# LB_BIT_iX_1IN_1OUT-SMALL-v03_1_1x.net
KiCad netlist of a schematic drawn in EAGLE
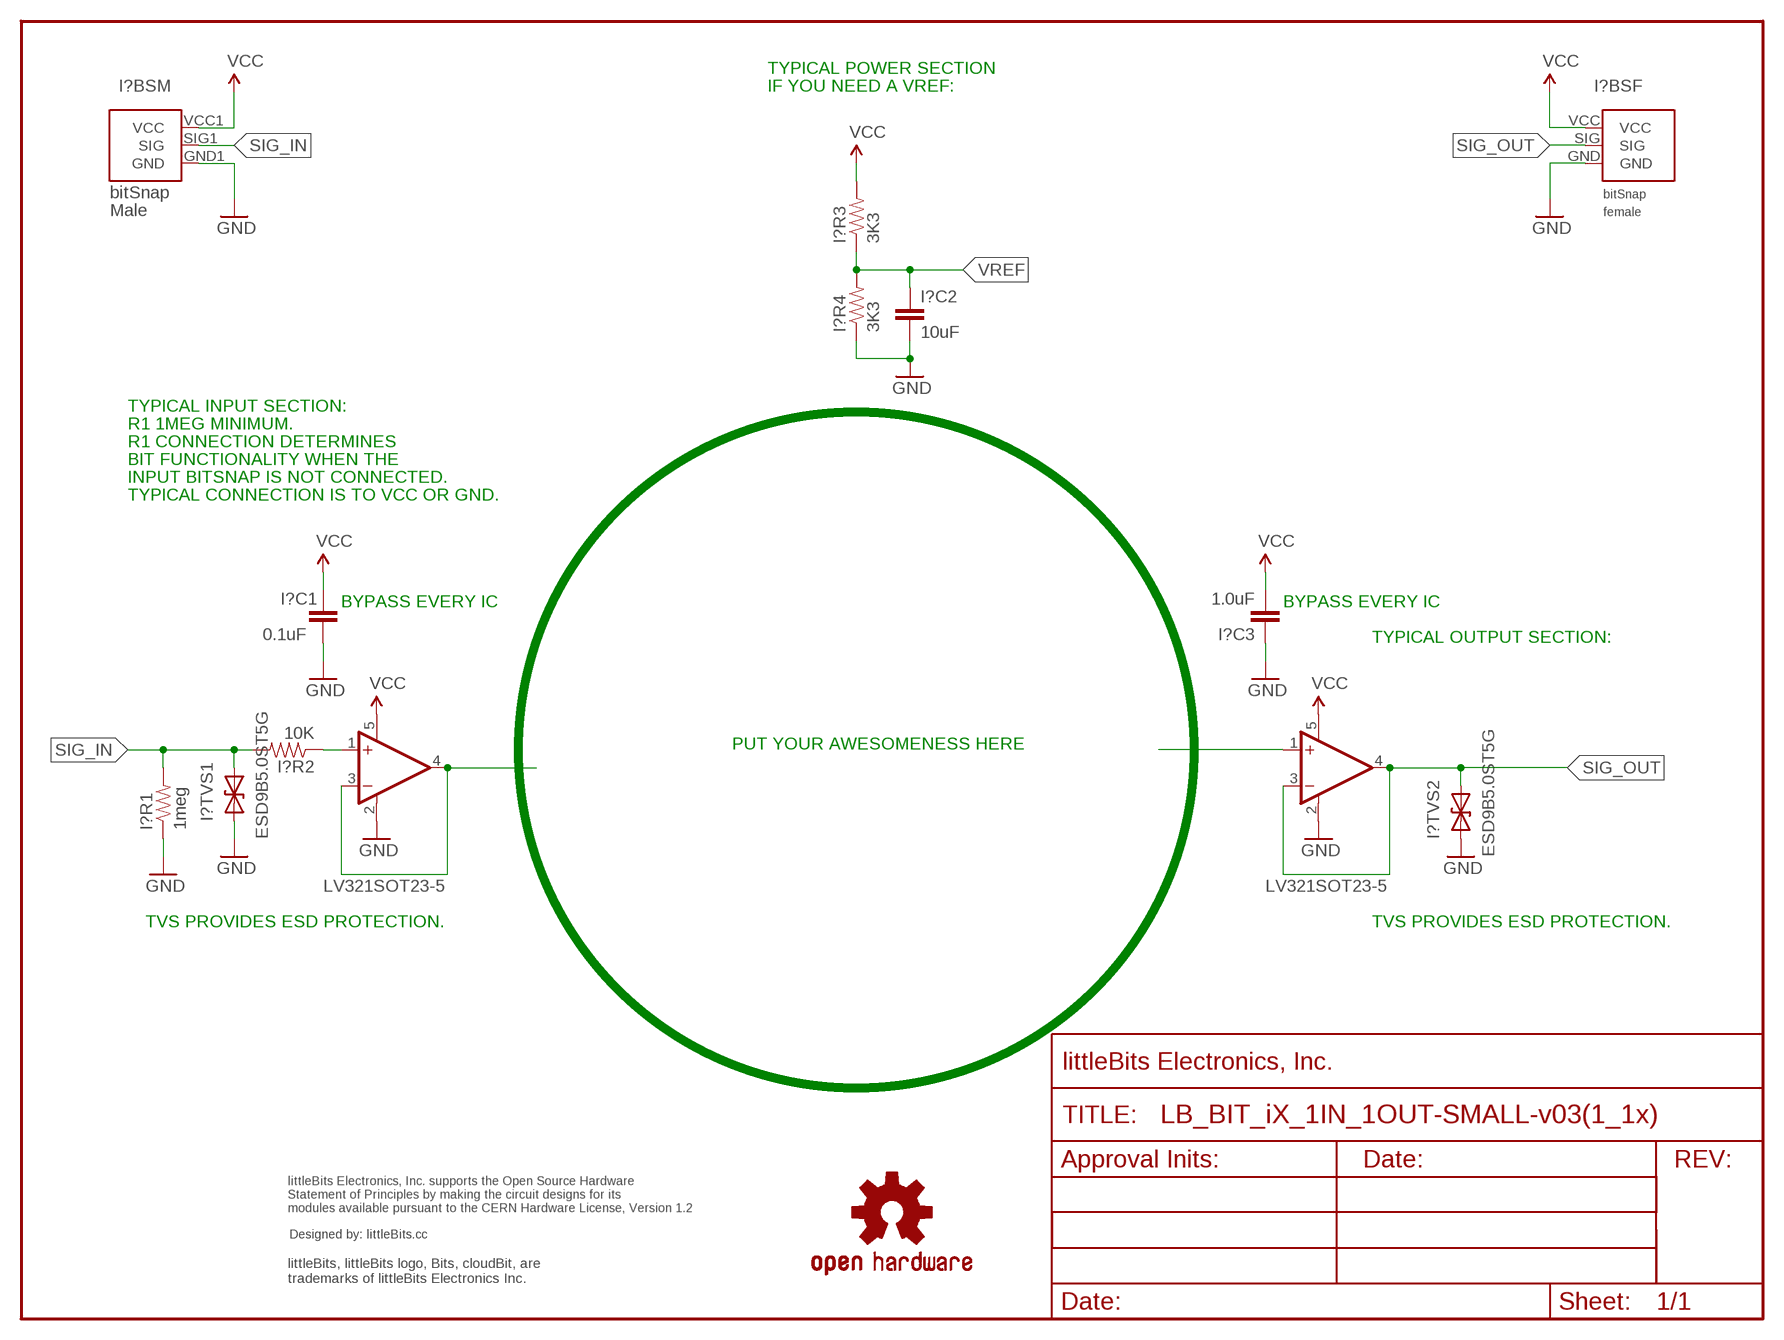
[diagram p0: schematic, sheet 1]

(export (version "E")
  (design (tool "Eeschema 10.0.6"))
  (components
    (comp (ref "I?BSF")
      (value "BITSNAP_V03_FEMALE")
      (footprint "eagle-import:BITSNAP_V03_FEMALE")
      (libsource (lib "eagle-import") (part "BITSNAP_V03_FEMALE"))
    )
    (comp (ref "I?BSM")
      (value "BITSNAP_V03_MALE")
      (footprint "eagle-import:BITSNAP_V03_MALE")
      (libsource (lib "eagle-import") (part "BITSNAP_V03_MALE"))
    )
    (comp (ref "I?C1")
      (value "0.1uF")
      (footprint "eagle-import:CAP-0603")
      (libsource (lib "eagle-import") (part "CAPCAP-0603"))
    )
    (comp (ref "I?C2")
      (value "10uF")
      (footprint "eagle-import:CAP-0603")
      (libsource (lib "eagle-import") (part "CAPCAP-0603"))
    )
    (comp (ref "I?C3")
      (value "1.0uF")
      (footprint "eagle-import:CAP-0603")
      (libsource (lib "eagle-import") (part "CAPCAP-0603"))
    )
    (comp (ref "I?R1")
      (value "1meg")
      (footprint "eagle-import:RES-0603")
      (libsource (lib "eagle-import") (part "RESISTOR0603"))
    )
    (comp (ref "I?R2")
      (value "10K")
      (footprint "eagle-import:RES-0603")
      (libsource (lib "eagle-import") (part "RESISTOR0603"))
    )
    (comp (ref "I?R3")
      (value "3K3")
      (footprint "eagle-import:RES-0603")
      (libsource (lib "eagle-import") (part "RESISTOR0603"))
    )
    (comp (ref "I?R4")
      (value "3K3")
      (footprint "eagle-import:RES-0603")
      (libsource (lib "eagle-import") (part "RESISTOR0603"))
    )
    (comp (ref "I?TVS1")
      (value "ESD9B5.0ST5G")
      (footprint "eagle-import:SOD-923")
      (libsource (lib "eagle-import") (part "DIODE-TVSSOD-923"))
    )
    (comp (ref "I?TVS2")
      (value "ESD9B5.0ST5G")
      (footprint "eagle-import:SOD-923")
      (libsource (lib "eagle-import") (part "DIODE-TVSSOD-923"))
    )
    (comp (ref "U$1")
      (value "OSHW-LOGOL")
      (footprint "eagle-import:OSHW-LOGO-L")
      (libsource (lib "eagle-import") (part "OSHW-LOGOL"))
    )
    (comp (ref "U$2")
      (value "OSHWCREDIT")
      (footprint "eagle-import:OSHWCREDIT")
      (libsource (lib "eagle-import") (part "OSHWCREDIT"))
    )
    (comp (ref "U$3")
      (value "FRAME-LETTER")
      (footprint "eagle-import:FABDWG01-OHW")
      (libsource (lib "eagle-import") (part "FRAME-LETTER"))
    )
    (comp (ref "U1")
      (value "LV321SOT23-5")
      (footprint "eagle-import:SOT23-5")
      (libsource (lib "eagle-import") (part "LV321SOT23-5"))
    )
    (comp (ref "U2")
      (value "LV321SOT23-5")
      (footprint "eagle-import:SOT23-5")
      (libsource (lib "eagle-import") (part "LV321SOT23-5"))
    )
  )
  (nets
    (net (code "1") (name "GND") (class "Default")
      (node (ref "I?BSF") (pin "GND") (pinfunction "GND_GND") (pintype "bidirectional"))
      (node (ref "I?BSM") (pin "GND1") (pinfunction "GND_GND1") (pintype "bidirectional"))
      (node (ref "I?C1") (pin "2") (pinfunction "2_2") (pintype "passive"))
      (node (ref "I?C2") (pin "2") (pinfunction "2_2") (pintype "passive"))
      (node (ref "I?C3") (pin "1") (pinfunction "1_1") (pintype "passive"))
      (node (ref "I?R1") (pin "1") (pinfunction "1_1") (pintype "passive"))
      (node (ref "I?R4") (pin "1") (pinfunction "1_1") (pintype "passive"))
      (node (ref "I?TVS1") (pin "1") (pinfunction "A_1") (pintype "passive"))
      (node (ref "I?TVS2") (pin "1") (pinfunction "A_1") (pintype "passive"))
      (node (ref "U1") (pin "2") (pinfunction "V-_2") (pintype "power_in"))
      (node (ref "U2") (pin "2") (pinfunction "V-_2") (pintype "power_in"))
    )
    (net (code "2") (name "Net-(U1-+IN)") (class "Default")
      (node (ref "I?R2") (pin "1") (pinfunction "1_1") (pintype "passive"))
      (node (ref "U1") (pin "1") (pinfunction "+IN_1") (pintype "input"))
    )
    (net (code "3") (name "Net-(U1--IN)") (class "Default")
      (node (ref "U1") (pin "3") (pinfunction "-IN_3") (pintype "input"))
      (node (ref "U1") (pin "4") (pinfunction "OUT_4") (pintype "output"))
    )
    (net (code "4") (name "SIG_IN") (class "Default")
      (node (ref "I?BSM") (pin "SIG1") (pinfunction "SIG_SIG1") (pintype "bidirectional"))
      (node (ref "I?R1") (pin "2") (pinfunction "2_2") (pintype "passive"))
      (node (ref "I?R2") (pin "2") (pinfunction "2_2") (pintype "passive"))
      (node (ref "I?TVS1") (pin "2") (pinfunction "C_2") (pintype "passive"))
    )
    (net (code "5") (name "SIG_OUT") (class "Default")
      (node (ref "I?BSF") (pin "SIG") (pinfunction "SIG_SIG") (pintype "bidirectional"))
      (node (ref "I?TVS2") (pin "2") (pinfunction "C_2") (pintype "passive"))
      (node (ref "U2") (pin "3") (pinfunction "-IN_3") (pintype "input"))
      (node (ref "U2") (pin "4") (pinfunction "OUT_4") (pintype "output"))
    )
    (net (code "6") (name "VCC") (class "Default")
      (node (ref "I?BSF") (pin "VCC") (pinfunction "VCC_VCC") (pintype "bidirectional"))
      (node (ref "I?BSM") (pin "VCC1") (pinfunction "VCC_VCC1") (pintype "bidirectional"))
      (node (ref "I?C1") (pin "1") (pinfunction "1_1") (pintype "passive"))
      (node (ref "I?C3") (pin "2") (pinfunction "2_2") (pintype "passive"))
      (node (ref "I?R3") (pin "2") (pinfunction "2_2") (pintype "passive"))
      (node (ref "U1") (pin "5") (pinfunction "V+_5") (pintype "power_in"))
      (node (ref "U2") (pin "5") (pinfunction "V+_5") (pintype "power_in"))
    )
    (net (code "7") (name "VREF") (class "Default")
      (node (ref "I?C2") (pin "1") (pinfunction "1_1") (pintype "passive"))
      (node (ref "I?R3") (pin "1") (pinfunction "1_1") (pintype "passive"))
      (node (ref "I?R4") (pin "2") (pinfunction "2_2") (pintype "passive"))
    )
    (net (code "8") (name "unconnected-(U2-+IN-Pad1)") (class "Default")
      (node (ref "U2") (pin "1") (pinfunction "+IN_1") (pintype "input"))
    )
  )
)
